# CLOCK_GENERATOR.net
KiCad netlist of a schematic drawn in Altium Designer
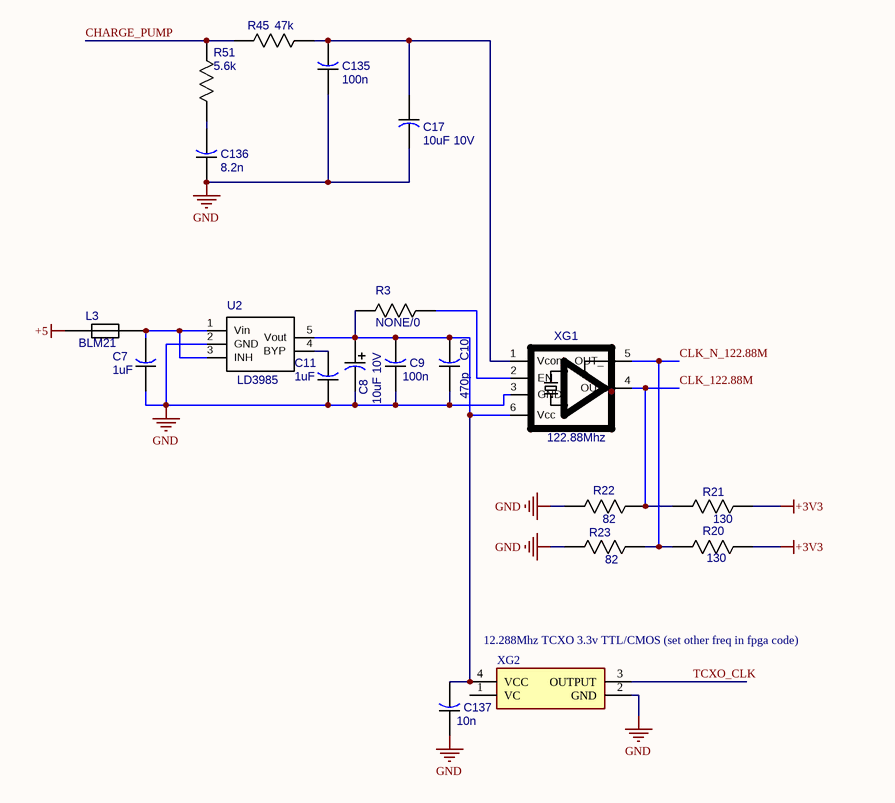
[diagram p0: CLOCK_GENERATOR.SchDoc]

(export (version "E")
  (design (tool "Eeschema 10.0.6"))
  (components
    (comp (ref "C7")
      (value "1uF")
      (footprint "CAP_0805")
      (description "CAP_0805")
      (libsource (lib "*") (part "CAP_0805"))
    )
    (comp (ref "C8")
      (value "10uF 10V")
      (footprint "CAPAE_4.3x4.3h5.4")
      (description "CAPAE_4.3x4.3h5.4")
      (libsource (lib "*") (part "CAPAE_4.3x4.3h5.4"))
    )
    (comp (ref "C9")
      (value "100n")
      (footprint "CAP_0805")
      (description "CAP_0805")
      (libsource (lib "*") (part "CAP_0805"))
    )
    (comp (ref "C10")
      (value "470p")
      (footprint "CAP_0805")
      (description "CAP_0805")
      (libsource (lib "*") (part "CAP_0805"))
    )
    (comp (ref "C11")
      (value "1uF")
      (footprint "CAP_0805")
      (description "CAP_0805")
      (libsource (lib "*") (part "CAP_0805"))
    )
    (comp (ref "C17")
      (value "10uF 10V")
      (footprint "CAP_0805")
      (description "CAP_0805")
      (libsource (lib "*") (part "CAP_0805"))
    )
    (comp (ref "C135")
      (value "100n")
      (footprint "CAP_0805")
      (description "CAP_0805")
      (libsource (lib "*") (part "CAP_0805"))
    )
    (comp (ref "C136")
      (value "8.2n")
      (footprint "CAP_0805")
      (description "CAP_0805")
      (libsource (lib "*") (part "CAP_0805"))
    )
    (comp (ref "C137")
      (value "10n")
      (footprint "CAP_0805")
      (description "CAP_0805")
      (libsource (lib "*") (part "CAP_0805"))
    )
    (comp (ref "L3")
      (value "BLM21")
      (footprint "CAP_0805")
      (libsource (lib "MOTHERBOARD_1") (part "IND_FERRITE_BEAD"))
    )
    (comp (ref "R3")
      (value "NONE/0")
      (footprint "RES_0805")
      (description "By used crystal")
      (fields (field (name "Comment") "0/NONE"))
      (libsource (lib "*") (part "RES_0805"))
    )
    (comp (ref "R20")
      (value "130")
      (footprint "RES_0805")
      (description "RES_0805")
      (libsource (lib "*") (part "RES_0805"))
    )
    (comp (ref "R21")
      (value "130")
      (footprint "RES_0805")
      (description "RES_0805")
      (libsource (lib "*") (part "RES_0805"))
    )
    (comp (ref "R22")
      (value "82")
      (footprint "RES_0805")
      (description "RES_0805")
      (libsource (lib "*") (part "RES_0805"))
    )
    (comp (ref "R23")
      (value "82")
      (footprint "RES_0805")
      (description "RES_0805")
      (libsource (lib "*") (part "RES_0805"))
    )
    (comp (ref "R45")
      (value "47k")
      (footprint "RES_0805")
      (description "RES_0805")
      (libsource (lib "*") (part "RES_0805"))
    )
    (comp (ref "R51")
      (value "5.6k")
      (footprint "RES_0805")
      (description "RES_0805")
      (libsource (lib "*") (part "RES_0805"))
    )
    (comp (ref "U2") (value "LD3985") (footprint "LD3985") (libsource (lib "*") (part "LD3985")))
    (comp (ref "XG1")
      (value "122.88Mhz")
      (footprint "NV7050SA")
      (description "NV7050SA\r\nVG-4513CA-122.8800M-GGCT3")
      (libsource (lib "*") (part "NV7050SA"))
    )
    (comp (ref "XG2")
      (value "12.288Mhz TCXO 3.3v TTL/CMOS (set other freq in fpga code)")
      (footprint "SamacSys:581L200X2ITT")
      (description "Crystal or Oscillator")
      (fields
        (field (name "MANUFACTURER_PART_NUMBER") "581L200X2ITT")
        (field (name "MOUSER PART NUMBER") "774-581L200X2ITT")
      )
      (libsource (lib "*") (part "581L200X2ITT"))
    )
  )
  (nets
    (net (code "1") (name "+3V3") (class "Default")
      (node (ref "R20") (pin "1") (pinfunction "1_1") (pintype "passive"))
      (node (ref "R21") (pin "1") (pinfunction "1_1") (pintype "passive"))
    )
    (net (code "2") (name "+5") (class "Default")
      (node (ref "L3") (pin "1") (pinfunction "1_1") (pintype "passive"))
    )
    (net (code "3") (name "/CHARGE_PUMP") (class "Default")
      (node (ref "R45") (pin "1") (pinfunction "1_1") (pintype "passive"))
      (node (ref "R51") (pin "1") (pinfunction "1_1") (pintype "passive"))
    )
    (net (code "4") (name "/CLK_122.88M") (class "Default")
      (node (ref "R21") (pin "2") (pinfunction "2_2") (pintype "passive"))
      (node (ref "R22") (pin "1") (pinfunction "1_1") (pintype "passive"))
      (node (ref "XG1") (pin "4") (pinfunction "OUT_4") (pintype "passive"))
    )
    (net (code "5") (name "/CLK_N_122.88M") (class "Default")
      (node (ref "R20") (pin "2") (pinfunction "2_2") (pintype "passive"))
      (node (ref "R23") (pin "1") (pinfunction "1_1") (pintype "passive"))
      (node (ref "XG1") (pin "5") (pinfunction "OUT__5") (pintype "passive"))
    )
    (net (code "6") (name "/TCXO_CLK") (class "Default")
      (node (ref "XG2") (pin "3") (pinfunction "OUTPUT_3") (pintype "passive"))
    )
    (net (code "7") (name "GND") (class "Default")
      (node (ref "C10") (pin "1") (pinfunction "1_1") (pintype "passive"))
      (node (ref "C11") (pin "1") (pinfunction "1_1") (pintype "passive"))
      (node (ref "C135") (pin "1") (pinfunction "1_1") (pintype "passive"))
      (node (ref "C136") (pin "1") (pinfunction "1_1") (pintype "passive"))
      (node (ref "C137") (pin "1") (pinfunction "1_1") (pintype "passive"))
      (node (ref "C17") (pin "2") (pinfunction "2_2") (pintype "passive"))
      (node (ref "C7") (pin "1") (pinfunction "1_1") (pintype "passive"))
      (node (ref "C8") (pin "2") (pinfunction "MINUS_2") (pintype "passive"))
      (node (ref "C9") (pin "1") (pinfunction "1_1") (pintype "passive"))
      (node (ref "R22") (pin "2") (pinfunction "2_2") (pintype "passive"))
      (node (ref "R23") (pin "2") (pinfunction "2_2") (pintype "passive"))
      (node (ref "U2") (pin "2") (pinfunction "GND_2") (pintype "passive"))
      (node (ref "XG1") (pin "3") (pinfunction "GND_3") (pintype "passive"))
      (node (ref "XG2") (pin "2") (pinfunction "GND_2") (pintype "passive"))
    )
    (net (code "8") (name "Net-(C8-PLUS)") (class "Default")
      (node (ref "C10") (pin "2") (pinfunction "2_2") (pintype "passive"))
      (node (ref "C137") (pin "2") (pinfunction "2_2") (pintype "passive"))
      (node (ref "C8") (pin "1") (pinfunction "PLUS_1") (pintype "passive"))
      (node (ref "C9") (pin "2") (pinfunction "2_2") (pintype "passive"))
      (node (ref "R3") (pin "1") (pinfunction "1_1") (pintype "passive"))
      (node (ref "U2") (pin "5") (pinfunction "Vout_5") (pintype "passive"))
      (node (ref "XG1") (pin "6") (pinfunction "Vcc_6") (pintype "passive"))
      (node (ref "XG2") (pin "4") (pinfunction "VCC_4") (pintype "passive"))
    )
    (net (code "9") (name "Net-(C136-Pad2)") (class "Default")
      (node (ref "C136") (pin "2") (pinfunction "2_2") (pintype "passive"))
      (node (ref "R51") (pin "2") (pinfunction "2_2") (pintype "passive"))
    )
    (net (code "10") (name "Net-(U2-BYP)") (class "Default")
      (node (ref "C11") (pin "2") (pinfunction "2_2") (pintype "passive"))
      (node (ref "U2") (pin "4") (pinfunction "BYP_4") (pintype "passive"))
    )
    (net (code "11") (name "Net-(U2-INH)") (class "Default")
      (node (ref "C7") (pin "2") (pinfunction "2_2") (pintype "passive"))
      (node (ref "L3") (pin "2") (pinfunction "2_2") (pintype "passive"))
      (node (ref "U2") (pin "1") (pinfunction "Vin_1") (pintype "passive"))
      (node (ref "U2") (pin "3") (pinfunction "INH_3") (pintype "passive"))
    )
    (net (code "12") (name "Net-(XG1-EN)") (class "Default")
      (node (ref "R3") (pin "2") (pinfunction "2_2") (pintype "passive"))
      (node (ref "XG1") (pin "2") (pinfunction "EN_2") (pintype "passive"))
    )
    (net (code "13") (name "Net-(XG1-Vcont)") (class "Default")
      (node (ref "C135") (pin "2") (pinfunction "2_2") (pintype "passive"))
      (node (ref "C17") (pin "1") (pinfunction "1_1") (pintype "passive"))
      (node (ref "R45") (pin "2") (pinfunction "2_2") (pintype "passive"))
      (node (ref "XG1") (pin "1") (pinfunction "Vcont_1") (pintype "passive"))
    )
    (net (code "14") (name "unconnected-(XG2-VC-Pad1)") (class "Default")
      (node (ref "XG2") (pin "1") (pinfunction "VC_1") (pintype "passive"))
    )
  )
)
